# SCH_LightsGames_2023-01-02.net
KiCad netlist of a schematic drawn in EasyEDA
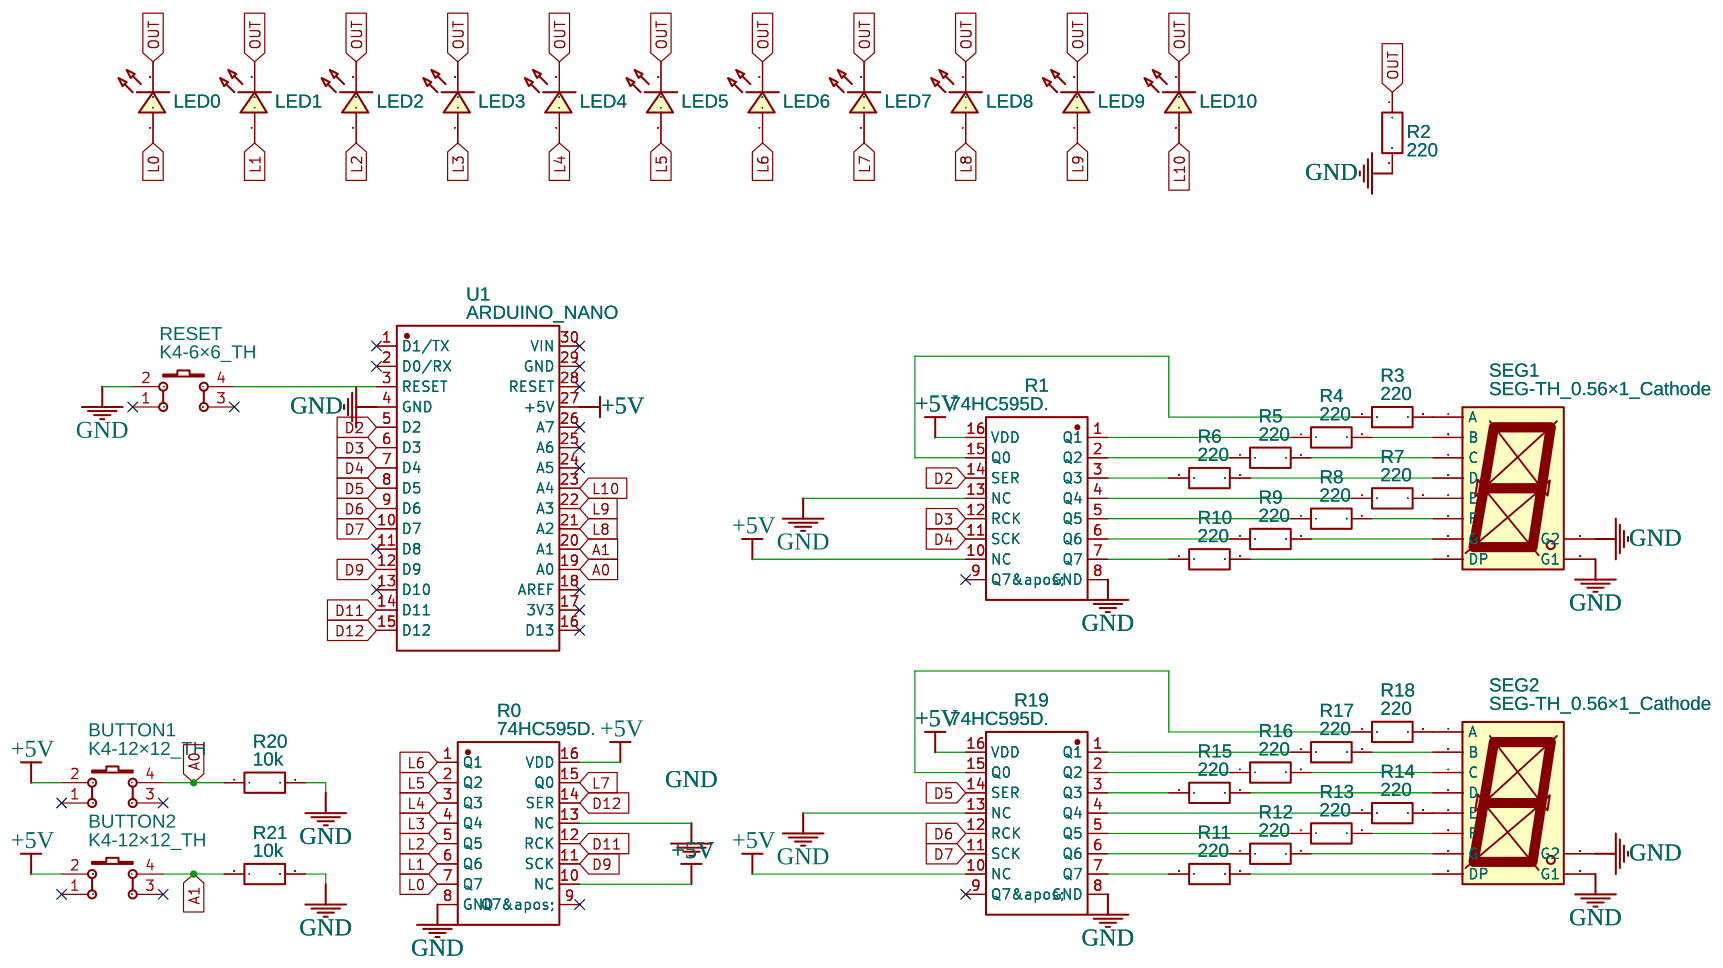
[diagram p0: schematic sheet]

(export (version "E")
  (design (tool "Eeschema 10.0.6"))
  (components
    (comp (ref "BUTTON1")
      (value "K4-12×12_TH")
      (fields
        (field (name "BOM_Manufacturer Part") "K2-1103DP-M4SW-04")
        (field (name "BOM_Supplier Part") "C128053")
      )
      (libsource (lib "") (part "K4-12×12_TH"))
    )
    (comp (ref "BUTTON2")
      (value "K4-12×12_TH")
      (fields
        (field (name "BOM_Manufacturer Part") "K2-1103DP-M4SW-04")
        (field (name "BOM_Supplier Part") "C128053")
      )
      (libsource (lib "") (part "K4-12×12_TH"))
    )
    (comp (ref "LED0")
      (value "LED-TH-5mm_R")
      (fields
        (field (name "BOM_Manufacturer Part") "333-2SURD/S530-A3")
        (field (name "BOM_Supplier Part") "C87271")
      )
      (libsource (lib "") (part "LED-TH-5mm_R"))
    )
    (comp (ref "LED1")
      (value "LED-TH-5mm_R")
      (fields
        (field (name "BOM_Manufacturer Part") "333-2SURD/S530-A3")
        (field (name "BOM_Supplier Part") "C87271")
      )
      (libsource (lib "") (part "LED-TH-5mm_R"))
    )
    (comp (ref "LED2")
      (value "LED-TH-5mm_R")
      (fields
        (field (name "BOM_Manufacturer Part") "333-2SURD/S530-A3")
        (field (name "BOM_Supplier Part") "C87271")
      )
      (libsource (lib "") (part "LED-TH-5mm_R"))
    )
    (comp (ref "LED3")
      (value "LED-TH-5mm_G")
      (fields
        (field (name "BOM_Manufacturer Part") "333-2SYGD/S530-E2")
        (field (name "BOM_Supplier Part") "C88163")
      )
      (libsource (lib "") (part "LED-TH-5mm_G"))
    )
    (comp (ref "LED4")
      (value "LED-TH-5mm_G")
      (fields
        (field (name "BOM_Manufacturer Part") "333-2SYGD/S530-E2")
        (field (name "BOM_Supplier Part") "C88163")
      )
      (libsource (lib "") (part "LED-TH-5mm_G"))
    )
    (comp (ref "LED5")
      (value "LED-TH-5mm_G")
      (fields
        (field (name "BOM_Manufacturer Part") "333-2SYGD/S530-E2")
        (field (name "BOM_Supplier Part") "C88163")
      )
      (libsource (lib "") (part "LED-TH-5mm_G"))
    )
    (comp (ref "LED6")
      (value "LED-TH-5mm_G")
      (fields
        (field (name "BOM_Manufacturer Part") "333-2SYGD/S530-E2")
        (field (name "BOM_Supplier Part") "C88163")
      )
      (libsource (lib "") (part "LED-TH-5mm_G"))
    )
    (comp (ref "LED7")
      (value "LED-TH-5mm_G")
      (fields
        (field (name "BOM_Manufacturer Part") "333-2SYGD/S530-E2")
        (field (name "BOM_Supplier Part") "C88163")
      )
      (libsource (lib "") (part "LED-TH-5mm_G"))
    )
    (comp (ref "LED8")
      (value "LED-TH-5mm_R")
      (fields
        (field (name "BOM_Manufacturer Part") "333-2SURD/S530-A3")
        (field (name "BOM_Supplier Part") "C87271")
      )
      (libsource (lib "") (part "LED-TH-5mm_R"))
    )
    (comp (ref "LED9")
      (value "LED-TH-5mm_R")
      (fields
        (field (name "BOM_Manufacturer Part") "333-2SURD/S530-A3")
        (field (name "BOM_Supplier Part") "C87271")
      )
      (libsource (lib "") (part "LED-TH-5mm_R"))
    )
    (comp (ref "LED10")
      (value "LED-TH-5mm_R")
      (fields
        (field (name "BOM_Manufacturer Part") "333-2SURD/S530-A3")
        (field (name "BOM_Supplier Part") "C87271")
      )
      (libsource (lib "") (part "LED-TH-5mm_R"))
    )
    (comp (ref "R0")
      (value "74HC595D.")
      (fields (field (name "BOM_Supplier Part") "C2929943"))
      (libsource (lib "") (part "74HC595D."))
    )
    (comp (ref "R1")
      (value "74HC595D.")
      (fields (field (name "BOM_Supplier Part") "C2929943"))
      (libsource (lib "") (part "74HC595D._1"))
    )
    (comp (ref "R2") (value "220") (libsource (lib "") (part "R_0603_EU_1")))
    (comp (ref "R3") (value "220") (libsource (lib "") (part "R_0603_EU")))
    (comp (ref "R4") (value "220") (libsource (lib "") (part "R_0603_EU")))
    (comp (ref "R5") (value "220") (libsource (lib "") (part "R_0603_EU")))
    (comp (ref "R6") (value "220") (libsource (lib "") (part "R_0603_EU")))
    (comp (ref "R7") (value "220") (libsource (lib "") (part "R_0603_EU")))
    (comp (ref "R8") (value "220") (libsource (lib "") (part "R_0603_EU")))
    (comp (ref "R9") (value "220") (libsource (lib "") (part "R_0603_EU")))
    (comp (ref "R10") (value "220") (libsource (lib "") (part "R_0603_EU")))
    (comp (ref "R11") (value "220") (libsource (lib "") (part "R_0603_EU")))
    (comp (ref "R12") (value "220") (libsource (lib "") (part "R_0603_EU")))
    (comp (ref "R13") (value "220") (libsource (lib "") (part "R_0603_EU")))
    (comp (ref "R14") (value "220") (libsource (lib "") (part "R_0603_EU")))
    (comp (ref "R15") (value "220") (libsource (lib "") (part "R_0603_EU")))
    (comp (ref "R16") (value "220") (libsource (lib "") (part "R_0603_EU")))
    (comp (ref "R17") (value "220") (libsource (lib "") (part "R_0603_EU")))
    (comp (ref "R18") (value "220") (libsource (lib "") (part "R_0603_EU")))
    (comp (ref "R19")
      (value "74HC595D.")
      (fields (field (name "BOM_Supplier Part") "C2929943"))
      (libsource (lib "") (part "74HC595D._1"))
    )
    (comp (ref "R20") (value "10k") (libsource (lib "") (part "R_0603_EU")))
    (comp (ref "R21") (value "10k") (libsource (lib "") (part "R_0603_EU")))
    (comp (ref "RESET")
      (value "K4-6×6_TH")
      (fields
        (field (name "BOM_Manufacturer Part") "K2-1102DP-E4SW-04")
        (field (name "BOM_Supplier Part") "C136684")
      )
      (libsource (lib "") (part "K4-6×6_TH"))
    )
    (comp (ref "SEG1")
      (value "SEG-TH_0.56×1_Cathode")
      (fields (field (name "BOM_Supplier Part") "C8093"))
      (libsource (lib "") (part "SEG-TH_0.56×1_Cathode"))
    )
    (comp (ref "SEG2")
      (value "SEG-TH_0.56×1_Cathode")
      (fields (field (name "BOM_Supplier Part") "C8093"))
      (libsource (lib "") (part "SEG-TH_0.56×1_Cathode"))
    )
    (comp (ref "U1")
      (value "ARDUINO_NANO")
      (fields (field (name "BOM_Supplier Part") "C9900017879"))
      (libsource (lib "") (part "ARDUINO_NANO"))
    )
  )
  (nets
    (net (code "1") (name "+5V") (class "Default")
      (node (ref "BUTTON1") (pin "2") (pinfunction "2_2") (pintype "unspecified"))
      (node (ref "BUTTON2") (pin "2") (pinfunction "2_2") (pintype "unspecified"))
      (node (ref "R0") (pin "10") (pinfunction "NC_10") (pintype "unspecified"))
      (node (ref "R0") (pin "16") (pinfunction "VDD_16") (pintype "unspecified"))
      (node (ref "R1") (pin "10") (pinfunction "NC_10") (pintype "unspecified"))
      (node (ref "R1") (pin "16") (pinfunction "VDD_16") (pintype "unspecified"))
      (node (ref "R19") (pin "10") (pinfunction "NC_10") (pintype "unspecified"))
      (node (ref "R19") (pin "16") (pinfunction "VDD_16") (pintype "unspecified"))
      (node (ref "U1") (pin "27") (pinfunction "+5V_27") (pintype "unspecified"))
    )
    (net (code "2") (name "A0") (class "Default")
      (node (ref "BUTTON1") (pin "4") (pinfunction "4_4") (pintype "unspecified"))
      (node (ref "R20") (pin "1") (pinfunction "1_1") (pintype "unspecified"))
      (node (ref "U1") (pin "19") (pinfunction "A0_19") (pintype "unspecified"))
    )
    (net (code "3") (name "A1") (class "Default")
      (node (ref "BUTTON2") (pin "4") (pinfunction "4_4") (pintype "unspecified"))
      (node (ref "R21") (pin "1") (pinfunction "1_1") (pintype "unspecified"))
      (node (ref "U1") (pin "20") (pinfunction "A1_20") (pintype "unspecified"))
    )
    (net (code "4") (name "D2") (class "Default")
      (node (ref "R1") (pin "14") (pinfunction "SER_14") (pintype "unspecified"))
      (node (ref "U1") (pin "5") (pinfunction "D2_5") (pintype "unspecified"))
    )
    (net (code "5") (name "D3") (class "Default")
      (node (ref "R1") (pin "12") (pinfunction "RCK_12") (pintype "unspecified"))
      (node (ref "U1") (pin "6") (pinfunction "D3_6") (pintype "unspecified"))
    )
    (net (code "6") (name "D4") (class "Default")
      (node (ref "R1") (pin "11") (pinfunction "SCK_11") (pintype "unspecified"))
      (node (ref "U1") (pin "7") (pinfunction "D4_7") (pintype "unspecified"))
    )
    (net (code "7") (name "D5") (class "Default")
      (node (ref "R19") (pin "14") (pinfunction "SER_14") (pintype "unspecified"))
      (node (ref "U1") (pin "8") (pinfunction "D5_8") (pintype "unspecified"))
    )
    (net (code "8") (name "D6") (class "Default")
      (node (ref "R19") (pin "12") (pinfunction "RCK_12") (pintype "unspecified"))
      (node (ref "U1") (pin "9") (pinfunction "D6_9") (pintype "unspecified"))
    )
    (net (code "9") (name "D7") (class "Default")
      (node (ref "R19") (pin "11") (pinfunction "SCK_11") (pintype "unspecified"))
      (node (ref "U1") (pin "10") (pinfunction "D7_10") (pintype "unspecified"))
    )
    (net (code "10") (name "D9") (class "Default")
      (node (ref "R0") (pin "11") (pinfunction "SCK_11") (pintype "unspecified"))
      (node (ref "U1") (pin "12") (pinfunction "D9_12") (pintype "unspecified"))
    )
    (net (code "11") (name "D11") (class "Default")
      (node (ref "R0") (pin "12") (pinfunction "RCK_12") (pintype "unspecified"))
      (node (ref "U1") (pin "14") (pinfunction "D11_14") (pintype "unspecified"))
    )
    (net (code "12") (name "D12") (class "Default")
      (node (ref "R0") (pin "14") (pinfunction "SER_14") (pintype "unspecified"))
      (node (ref "U1") (pin "15") (pinfunction "D12_15") (pintype "unspecified"))
    )
    (net (code "13") (name "GND") (class "Default")
      (node (ref "R0") (pin "13") (pinfunction "NC_13") (pintype "unspecified"))
      (node (ref "R0") (pin "8") (pinfunction "GND_8") (pintype "unspecified"))
      (node (ref "R1") (pin "13") (pinfunction "NC_13") (pintype "unspecified"))
      (node (ref "R1") (pin "8") (pinfunction "GND_8") (pintype "unspecified"))
      (node (ref "R19") (pin "13") (pinfunction "NC_13") (pintype "unspecified"))
      (node (ref "R19") (pin "8") (pinfunction "GND_8") (pintype "unspecified"))
      (node (ref "R2") (pin "2") (pinfunction "2_2") (pintype "unspecified"))
      (node (ref "R20") (pin "2") (pinfunction "2_2") (pintype "unspecified"))
      (node (ref "R21") (pin "2") (pinfunction "2_2") (pintype "unspecified"))
      (node (ref "RESET") (pin "2") (pinfunction "2_2") (pintype "unspecified"))
      (node (ref "SEG1") (pin "3") (pinfunction "G1_3") (pintype "unspecified"))
      (node (ref "SEG1") (pin "8") (pinfunction "G2_8") (pintype "unspecified"))
      (node (ref "SEG2") (pin "3") (pinfunction "G1_3") (pintype "unspecified"))
      (node (ref "SEG2") (pin "8") (pinfunction "G2_8") (pintype "unspecified"))
      (node (ref "U1") (pin "4") (pinfunction "GND_4") (pintype "unspecified"))
    )
    (net (code "14") (name "L0") (class "Default")
      (node (ref "LED0") (pin "1") (pinfunction "1_1") (pintype "unspecified"))
      (node (ref "R0") (pin "7") (pinfunction "Q7_7") (pintype "unspecified"))
    )
    (net (code "15") (name "L1") (class "Default")
      (node (ref "LED1") (pin "1") (pinfunction "1_1") (pintype "unspecified"))
      (node (ref "R0") (pin "6") (pinfunction "Q6_6") (pintype "unspecified"))
    )
    (net (code "16") (name "L2") (class "Default")
      (node (ref "LED2") (pin "1") (pinfunction "1_1") (pintype "unspecified"))
      (node (ref "R0") (pin "5") (pinfunction "Q5_5") (pintype "unspecified"))
    )
    (net (code "17") (name "L3") (class "Default")
      (node (ref "LED3") (pin "1") (pinfunction "1_1") (pintype "unspecified"))
      (node (ref "R0") (pin "4") (pinfunction "Q4_4") (pintype "unspecified"))
    )
    (net (code "18") (name "L4") (class "Default")
      (node (ref "LED4") (pin "1") (pinfunction "1_1") (pintype "unspecified"))
      (node (ref "R0") (pin "3") (pinfunction "Q3_3") (pintype "unspecified"))
    )
    (net (code "19") (name "L5") (class "Default")
      (node (ref "LED5") (pin "1") (pinfunction "1_1") (pintype "unspecified"))
      (node (ref "R0") (pin "2") (pinfunction "Q2_2") (pintype "unspecified"))
    )
    (net (code "20") (name "L6") (class "Default")
      (node (ref "LED6") (pin "1") (pinfunction "1_1") (pintype "unspecified"))
      (node (ref "R0") (pin "1") (pinfunction "Q1_1") (pintype "unspecified"))
    )
    (net (code "21") (name "L7") (class "Default")
      (node (ref "LED7") (pin "1") (pinfunction "1_1") (pintype "unspecified"))
      (node (ref "R0") (pin "15") (pinfunction "Q0_15") (pintype "unspecified"))
    )
    (net (code "22") (name "L8") (class "Default")
      (node (ref "LED8") (pin "1") (pinfunction "1_1") (pintype "unspecified"))
      (node (ref "U1") (pin "21") (pinfunction "A2_21") (pintype "unspecified"))
    )
    (net (code "23") (name "L9") (class "Default")
      (node (ref "LED9") (pin "1") (pinfunction "1_1") (pintype "unspecified"))
      (node (ref "U1") (pin "22") (pinfunction "A3_22") (pintype "unspecified"))
    )
    (net (code "24") (name "L10") (class "Default")
      (node (ref "LED10") (pin "1") (pinfunction "1_1") (pintype "unspecified"))
      (node (ref "U1") (pin "23") (pinfunction "A4_23") (pintype "unspecified"))
    )
    (net (code "25") (name "Net-(R1-Q0)") (class "Default")
      (node (ref "R1") (pin "15") (pinfunction "Q0_15") (pintype "unspecified"))
      (node (ref "R3") (pin "1") (pinfunction "1_1") (pintype "unspecified"))
    )
    (net (code "26") (name "Net-(R1-Q1)") (class "Default")
      (node (ref "R1") (pin "1") (pinfunction "Q1_1") (pintype "unspecified"))
      (node (ref "R4") (pin "1") (pinfunction "1_1") (pintype "unspecified"))
    )
    (net (code "27") (name "Net-(R1-Q2)") (class "Default")
      (node (ref "R1") (pin "2") (pinfunction "Q2_2") (pintype "unspecified"))
      (node (ref "R5") (pin "1") (pinfunction "1_1") (pintype "unspecified"))
    )
    (net (code "28") (name "Net-(R1-Q3)") (class "Default")
      (node (ref "R1") (pin "3") (pinfunction "Q3_3") (pintype "unspecified"))
      (node (ref "R6") (pin "1") (pinfunction "1_1") (pintype "unspecified"))
    )
    (net (code "29") (name "Net-(R1-Q4)") (class "Default")
      (node (ref "R1") (pin "4") (pinfunction "Q4_4") (pintype "unspecified"))
      (node (ref "R7") (pin "1") (pinfunction "1_1") (pintype "unspecified"))
    )
    (net (code "30") (name "Net-(R1-Q5)") (class "Default")
      (node (ref "R1") (pin "5") (pinfunction "Q5_5") (pintype "unspecified"))
      (node (ref "R8") (pin "1") (pinfunction "1_1") (pintype "unspecified"))
    )
    (net (code "31") (name "Net-(R1-Q6)") (class "Default")
      (node (ref "R1") (pin "6") (pinfunction "Q6_6") (pintype "unspecified"))
      (node (ref "R9") (pin "1") (pinfunction "1_1") (pintype "unspecified"))
    )
    (net (code "32") (name "Net-(R1-Q7)") (class "Default")
      (node (ref "R1") (pin "7") (pinfunction "Q7_7") (pintype "unspecified"))
      (node (ref "R10") (pin "1") (pinfunction "1_1") (pintype "unspecified"))
    )
    (net (code "33") (name "Net-(R19-Q0)") (class "Default")
      (node (ref "R18") (pin "1") (pinfunction "1_1") (pintype "unspecified"))
      (node (ref "R19") (pin "15") (pinfunction "Q0_15") (pintype "unspecified"))
    )
    (net (code "34") (name "Net-(R19-Q1)") (class "Default")
      (node (ref "R17") (pin "1") (pinfunction "1_1") (pintype "unspecified"))
      (node (ref "R19") (pin "1") (pinfunction "Q1_1") (pintype "unspecified"))
    )
    (net (code "35") (name "Net-(R19-Q2)") (class "Default")
      (node (ref "R16") (pin "1") (pinfunction "1_1") (pintype "unspecified"))
      (node (ref "R19") (pin "2") (pinfunction "Q2_2") (pintype "unspecified"))
    )
    (net (code "36") (name "Net-(R19-Q3)") (class "Default")
      (node (ref "R15") (pin "1") (pinfunction "1_1") (pintype "unspecified"))
      (node (ref "R19") (pin "3") (pinfunction "Q3_3") (pintype "unspecified"))
    )
    (net (code "37") (name "Net-(R19-Q4)") (class "Default")
      (node (ref "R14") (pin "1") (pinfunction "1_1") (pintype "unspecified"))
      (node (ref "R19") (pin "4") (pinfunction "Q4_4") (pintype "unspecified"))
    )
    (net (code "38") (name "Net-(R19-Q5)") (class "Default")
      (node (ref "R13") (pin "1") (pinfunction "1_1") (pintype "unspecified"))
      (node (ref "R19") (pin "5") (pinfunction "Q5_5") (pintype "unspecified"))
    )
    (net (code "39") (name "Net-(R19-Q6)") (class "Default")
      (node (ref "R12") (pin "1") (pinfunction "1_1") (pintype "unspecified"))
      (node (ref "R19") (pin "6") (pinfunction "Q6_6") (pintype "unspecified"))
    )
    (net (code "40") (name "Net-(R19-Q7)") (class "Default")
      (node (ref "R11") (pin "1") (pinfunction "1_1") (pintype "unspecified"))
      (node (ref "R19") (pin "7") (pinfunction "Q7_7") (pintype "unspecified"))
    )
    (net (code "41") (name "Net-(RESET-Pad4)") (class "Default")
      (node (ref "RESET") (pin "4") (pinfunction "4_4") (pintype "unspecified"))
      (node (ref "U1") (pin "3") (pinfunction "RESET_3") (pintype "unspecified"))
    )
    (net (code "42") (name "Net-(SEG1-A)") (class "Default")
      (node (ref "R3") (pin "2") (pinfunction "2_2") (pintype "unspecified"))
      (node (ref "SEG1") (pin "7") (pinfunction "A_7") (pintype "unspecified"))
    )
    (net (code "43") (name "Net-(SEG1-B)") (class "Default")
      (node (ref "R4") (pin "2") (pinfunction "2_2") (pintype "unspecified"))
      (node (ref "SEG1") (pin "6") (pinfunction "B_6") (pintype "unspecified"))
    )
    (net (code "44") (name "Net-(SEG1-C)") (class "Default")
      (node (ref "R5") (pin "2") (pinfunction "2_2") (pintype "unspecified"))
      (node (ref "SEG1") (pin "4") (pinfunction "C_4") (pintype "unspecified"))
    )
    (net (code "45") (name "Net-(SEG1-D)") (class "Default")
      (node (ref "R6") (pin "2") (pinfunction "2_2") (pintype "unspecified"))
      (node (ref "SEG1") (pin "2") (pinfunction "D_2") (pintype "unspecified"))
    )
    (net (code "46") (name "Net-(SEG1-DP)") (class "Default")
      (node (ref "R10") (pin "2") (pinfunction "2_2") (pintype "unspecified"))
      (node (ref "SEG1") (pin "5") (pinfunction "DP_5") (pintype "unspecified"))
    )
    (net (code "47") (name "Net-(SEG1-E)") (class "Default")
      (node (ref "R7") (pin "2") (pinfunction "2_2") (pintype "unspecified"))
      (node (ref "SEG1") (pin "1") (pinfunction "E_1") (pintype "unspecified"))
    )
    (net (code "48") (name "Net-(SEG1-F)") (class "Default")
      (node (ref "R8") (pin "2") (pinfunction "2_2") (pintype "unspecified"))
      (node (ref "SEG1") (pin "9") (pinfunction "F_9") (pintype "unspecified"))
    )
    (net (code "49") (name "Net-(SEG1-G)") (class "Default")
      (node (ref "R9") (pin "2") (pinfunction "2_2") (pintype "unspecified"))
      (node (ref "SEG1") (pin "10") (pinfunction "G_10") (pintype "unspecified"))
    )
    (net (code "50") (name "Net-(SEG2-A)") (class "Default")
      (node (ref "R18") (pin "2") (pinfunction "2_2") (pintype "unspecified"))
      (node (ref "SEG2") (pin "7") (pinfunction "A_7") (pintype "unspecified"))
    )
    (net (code "51") (name "Net-(SEG2-B)") (class "Default")
      (node (ref "R17") (pin "2") (pinfunction "2_2") (pintype "unspecified"))
      (node (ref "SEG2") (pin "6") (pinfunction "B_6") (pintype "unspecified"))
    )
    (net (code "52") (name "Net-(SEG2-C)") (class "Default")
      (node (ref "R16") (pin "2") (pinfunction "2_2") (pintype "unspecified"))
      (node (ref "SEG2") (pin "4") (pinfunction "C_4") (pintype "unspecified"))
    )
    (net (code "53") (name "Net-(SEG2-D)") (class "Default")
      (node (ref "R15") (pin "2") (pinfunction "2_2") (pintype "unspecified"))
      (node (ref "SEG2") (pin "2") (pinfunction "D_2") (pintype "unspecified"))
    )
    (net (code "54") (name "Net-(SEG2-DP)") (class "Default")
      (node (ref "R11") (pin "2") (pinfunction "2_2") (pintype "unspecified"))
      (node (ref "SEG2") (pin "5") (pinfunction "DP_5") (pintype "unspecified"))
    )
    (net (code "55") (name "Net-(SEG2-E)") (class "Default")
      (node (ref "R14") (pin "2") (pinfunction "2_2") (pintype "unspecified"))
      (node (ref "SEG2") (pin "1") (pinfunction "E_1") (pintype "unspecified"))
    )
    (net (code "56") (name "Net-(SEG2-F)") (class "Default")
      (node (ref "R13") (pin "2") (pinfunction "2_2") (pintype "unspecified"))
      (node (ref "SEG2") (pin "9") (pinfunction "F_9") (pintype "unspecified"))
    )
    (net (code "57") (name "Net-(SEG2-G)") (class "Default")
      (node (ref "R12") (pin "2") (pinfunction "2_2") (pintype "unspecified"))
      (node (ref "SEG2") (pin "10") (pinfunction "G_10") (pintype "unspecified"))
    )
    (net (code "58") (name "OUT") (class "Default")
      (node (ref "LED0") (pin "2") (pinfunction "2_2") (pintype "unspecified"))
      (node (ref "LED1") (pin "2") (pinfunction "2_2") (pintype "unspecified"))
      (node (ref "LED10") (pin "2") (pinfunction "2_2") (pintype "unspecified"))
      (node (ref "LED2") (pin "2") (pinfunction "2_2") (pintype "unspecified"))
      (node (ref "LED3") (pin "2") (pinfunction "2_2") (pintype "unspecified"))
      (node (ref "LED4") (pin "2") (pinfunction "2_2") (pintype "unspecified"))
      (node (ref "LED5") (pin "2") (pinfunction "2_2") (pintype "unspecified"))
      (node (ref "LED6") (pin "2") (pinfunction "2_2") (pintype "unspecified"))
      (node (ref "LED7") (pin "2") (pinfunction "2_2") (pintype "unspecified"))
      (node (ref "LED8") (pin "2") (pinfunction "2_2") (pintype "unspecified"))
      (node (ref "LED9") (pin "2") (pinfunction "2_2") (pintype "unspecified"))
      (node (ref "R2") (pin "1") (pinfunction "1_1") (pintype "unspecified"))
    )
    (net (code "59") (name "unconnected-(BUTTON1-Pad1)") (class "Default")
      (node (ref "BUTTON1") (pin "1") (pinfunction "1_1") (pintype "unspecified+no_connect"))
    )
    (net (code "60") (name "unconnected-(BUTTON1-Pad3)") (class "Default")
      (node (ref "BUTTON1") (pin "3") (pinfunction "3_3") (pintype "unspecified+no_connect"))
    )
    (net (code "61") (name "unconnected-(BUTTON2-Pad1)") (class "Default")
      (node (ref "BUTTON2") (pin "1") (pinfunction "1_1") (pintype "unspecified+no_connect"))
    )
    (net (code "62") (name "unconnected-(BUTTON2-Pad3)") (class "Default")
      (node (ref "BUTTON2") (pin "3") (pinfunction "3_3") (pintype "unspecified+no_connect"))
    )
    (net (code "63") (name "unconnected-(R0-Q7&apos;-Pad9)") (class "Default")
      (node (ref "R0") (pin "9") (pinfunction "Q7&apos;_9") (pintype "unspecified+no_connect"))
    )
    (net (code "64") (name "unconnected-(R1-Q7&apos;-Pad9)") (class "Default")
      (node (ref "R1") (pin "9") (pinfunction "Q7&apos;_9") (pintype "unspecified+no_connect"))
    )
    (net (code "65") (name "unconnected-(R19-Q7&apos;-Pad9)") (class "Default")
      (node (ref "R19") (pin "9") (pinfunction "Q7&apos;_9") (pintype "unspecified+no_connect"))
    )
    (net (code "66") (name "unconnected-(RESET-Pad1)") (class "Default")
      (node (ref "RESET") (pin "1") (pinfunction "1_1") (pintype "unspecified+no_connect"))
    )
    (net (code "67") (name "unconnected-(RESET-Pad3)") (class "Default")
      (node (ref "RESET") (pin "3") (pinfunction "3_3") (pintype "unspecified+no_connect"))
    )
    (net (code "68") (name "unconnected-(U1-3V3-Pad17)") (class "Default")
      (node (ref "U1") (pin "17") (pinfunction "3V3_17") (pintype "unspecified+no_connect"))
    )
    (net (code "69") (name "unconnected-(U1-A5-Pad24)") (class "Default")
      (node (ref "U1") (pin "24") (pinfunction "A5_24") (pintype "unspecified+no_connect"))
    )
    (net (code "70") (name "unconnected-(U1-A6-Pad25)") (class "Default")
      (node (ref "U1") (pin "25") (pinfunction "A6_25") (pintype "unspecified+no_connect"))
    )
    (net (code "71") (name "unconnected-(U1-A7-Pad26)") (class "Default")
      (node (ref "U1") (pin "26") (pinfunction "A7_26") (pintype "unspecified+no_connect"))
    )
    (net (code "72") (name "unconnected-(U1-AREF-Pad18)") (class "Default")
      (node (ref "U1") (pin "18") (pinfunction "AREF_18") (pintype "unspecified+no_connect"))
    )
    (net (code "73") (name "unconnected-(U1-D0{slash}RX-Pad2)") (class "Default")
      (node (ref "U1") (pin "2") (pinfunction "D0/RX_2") (pintype "unspecified+no_connect"))
    )
    (net (code "74") (name "unconnected-(U1-D1{slash}TX-Pad1)") (class "Default")
      (node (ref "U1") (pin "1") (pinfunction "D1/TX_1") (pintype "unspecified+no_connect"))
    )
    (net (code "75") (name "unconnected-(U1-D8-Pad11)") (class "Default")
      (node (ref "U1") (pin "11") (pinfunction "D8_11") (pintype "unspecified+no_connect"))
    )
    (net (code "76") (name "unconnected-(U1-D10-Pad13)") (class "Default")
      (node (ref "U1") (pin "13") (pinfunction "D10_13") (pintype "unspecified+no_connect"))
    )
    (net (code "77") (name "unconnected-(U1-D13-Pad16)") (class "Default")
      (node (ref "U1") (pin "16") (pinfunction "D13_16") (pintype "unspecified+no_connect"))
    )
    (net (code "78") (name "unconnected-(U1-GND-Pad29)") (class "Default")
      (node (ref "U1") (pin "29") (pinfunction "GND_29") (pintype "unspecified+no_connect"))
    )
    (net (code "79") (name "unconnected-(U1-RESET-Pad28)") (class "Default")
      (node (ref "U1") (pin "28") (pinfunction "RESET_28") (pintype "unspecified+no_connect"))
    )
    (net (code "80") (name "unconnected-(U1-VIN-Pad30)") (class "Default")
      (node (ref "U1") (pin "30") (pinfunction "VIN_30") (pintype "unspecified+no_connect"))
    )
  )
)
